# External_WatchDogs.net
KiCad netlist of a schematic drawn in Altium Designer
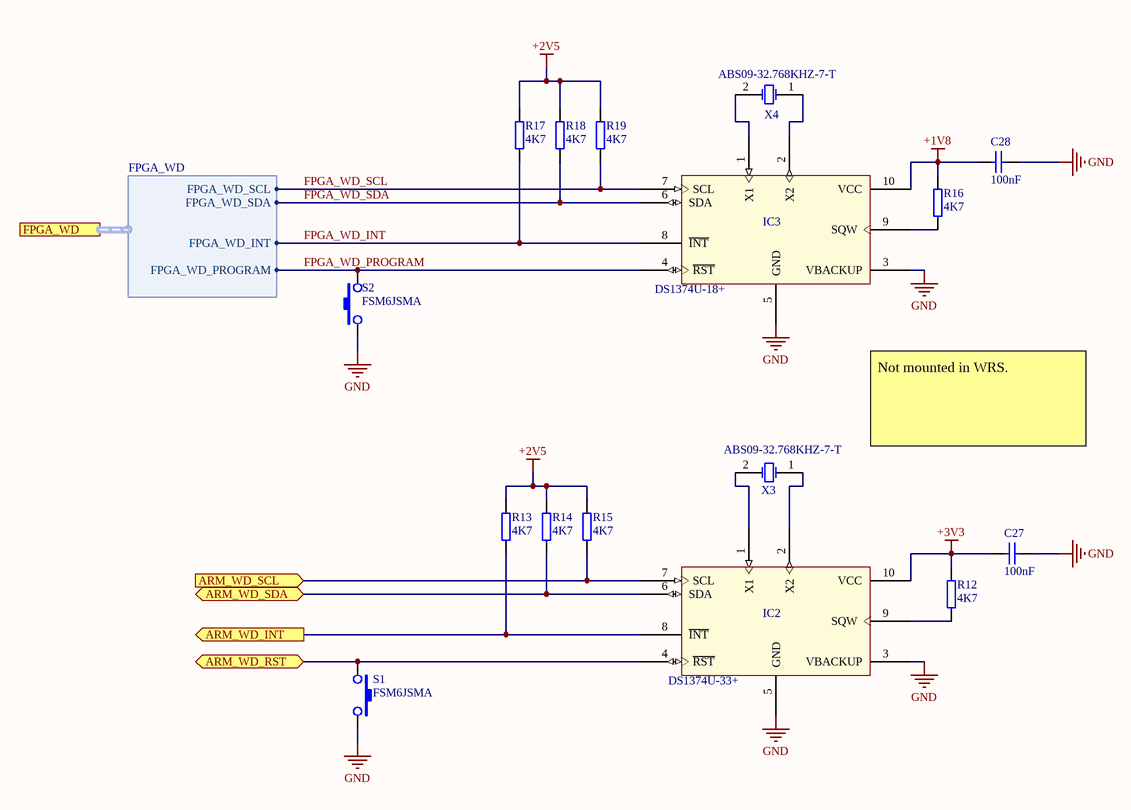
[diagram p0: External WatchDogs.SchDoc]

(export (version "E")
  (design (tool "Eeschema 10.0.6"))
  (components
    (comp (ref "C27")
      (value "100nF")
      (footprint "CC1005-0402")
      (description "Capacitor")
      (fields
        (field (name "TOLERANCE") "±10%")
        (field (name "VOLTAGE") "16V")
        (field (name "PUBLISHER") "Altium Limited")
      )
      (libsource (lib "wr_switch") (part "Cap"))
    )
    (comp (ref "C28")
      (value "100nF")
      (footprint "CC1005-0402")
      (description "Capacitor")
      (fields
        (field (name "TOLERANCE") "±10%")
        (field (name "VOLTAGE") "16V")
        (field (name "PUBLISHER") "Altium Limited")
      )
      (libsource (lib "wr_switch") (part "Cap"))
    )
    (comp (ref "IC2")
      (value "DS1374U-33+")
      (footprint "UMAX10")
      (description "I2C, 32 BIT BINARY COUNTER WATCHDOG RTC")
      (libsource (lib "wr_switch") (part "DS1374"))
    )
    (comp (ref "IC3")
      (value "DS1374U-18+")
      (footprint "UMAX10")
      (description "I2C, 32 BIT BINARY COUNTER WATCHDOG RTC")
      (libsource (lib "wr_switch") (part "DS1374"))
    )
    (comp (ref "R12")
      (value "4K7")
      (footprint "0402")
      (description "SMD Resistor")
      (fields (field (name "TOLERANCE") "±1%"))
      (libsource (lib "wr_switch") (part "RES_SMD"))
    )
    (comp (ref "R13")
      (value "4K7")
      (footprint "0402")
      (description "SMD Resistor")
      (fields (field (name "TOLERANCE") "±1%"))
      (libsource (lib "wr_switch") (part "RES_SMD"))
    )
    (comp (ref "R14")
      (value "4K7")
      (footprint "0402")
      (description "SMD Resistor")
      (fields (field (name "TOLERANCE") "±1%"))
      (libsource (lib "wr_switch") (part "RES_SMD"))
    )
    (comp (ref "R15")
      (value "4K7")
      (footprint "0402")
      (description "SMD Resistor")
      (fields (field (name "TOLERANCE") "±1%"))
      (libsource (lib "wr_switch") (part "RES_SMD"))
    )
    (comp (ref "R16")
      (value "4K7")
      (footprint "0402")
      (description "SMD Resistor")
      (fields (field (name "TOLERANCE") "±1%"))
      (libsource (lib "wr_switch") (part "RES_SMD"))
    )
    (comp (ref "R17")
      (value "4K7")
      (footprint "0402")
      (description "SMD Resistor")
      (fields (field (name "TOLERANCE") "±1%"))
      (libsource (lib "wr_switch") (part "RES_SMD"))
    )
    (comp (ref "R18")
      (value "4K7")
      (footprint "0402")
      (description "SMD Resistor")
      (fields (field (name "TOLERANCE") "±1%"))
      (libsource (lib "wr_switch") (part "RES_SMD"))
    )
    (comp (ref "R19")
      (value "4K7")
      (footprint "0402")
      (description "SMD Resistor")
      (fields (field (name "TOLERANCE") "±1%"))
      (libsource (lib "wr_switch") (part "RES_SMD"))
    )
    (comp (ref "S1")
      (value "FSM6JSMA")
      (footprint "7S_WR:SWITCH-FSM6JSMA")
      (description "Push button")
      (fields (field (name "MANUFACTURER") "Tyco Electronics"))
      (libsource (lib "wr_switch") (part "SW-PB"))
    )
    (comp (ref "S2")
      (value "FSM6JSMA")
      (footprint "7S_WR:SWITCH-FSM6JSMA")
      (description "Push button")
      (fields (field (name "MANUFACTURER") "Tyco Electronics"))
      (libsource (lib "wr_switch") (part "SW-PB"))
    )
    (comp (ref "X3")
      (value "ABS09-32.768KHZ-7-T")
      (footprint "XTAL_abs09")
      (description "Crystal Oscillator 7pF")
      (fields (field (name "MANUFACTURER") "Raltron") (field (name "PUBLISHER") "Altium Limited"))
      (libsource (lib "Miscellaneous Devices") (part "XTAL"))
    )
    (comp (ref "X4")
      (value "ABS09-32.768KHZ-7-T")
      (footprint "XTAL_abs09")
      (description "Crystal Oscillator 7pF")
      (fields (field (name "MANUFACTURER") "Raltron") (field (name "PUBLISHER") "Altium Limited"))
      (libsource (lib "Miscellaneous Devices") (part "XTAL"))
    )
  )
  (nets
    (net (code "2") (name "+1V8") (class "Default")
      (node (ref "C28") (pin "2") (pinfunction "2_2") (pintype "passive"))
      (node (ref "IC3") (pin "10") (pinfunction "VCC_10") (pintype "power_in"))
      (node (ref "R16") (pin "2") (pinfunction "2_2") (pintype "passive"))
    )
    (net (code "3") (name "+2V5") (class "Default")
      (node (ref "R13") (pin "2") (pinfunction "2_2") (pintype "passive"))
      (node (ref "R14") (pin "2") (pinfunction "2_2") (pintype "passive"))
      (node (ref "R15") (pin "2") (pinfunction "2_2") (pintype "passive"))
      (node (ref "R17") (pin "2") (pinfunction "2_2") (pintype "passive"))
      (node (ref "R18") (pin "2") (pinfunction "2_2") (pintype "passive"))
      (node (ref "R19") (pin "2") (pinfunction "2_2") (pintype "passive"))
    )
    (net (code "4") (name "+3V3") (class "Default")
      (node (ref "C27") (pin "2") (pinfunction "2_2") (pintype "passive"))
      (node (ref "IC2") (pin "10") (pinfunction "VCC_10") (pintype "power_in"))
      (node (ref "R12") (pin "2") (pinfunction "2_2") (pintype "passive"))
    )
    (net (code "5") (name "/ARM_WD_INT") (class "Default")
      (node (ref "IC2") (pin "8") (pinfunction "~{INT}_8") (pintype "open_collector"))
      (node (ref "R13") (pin "1") (pinfunction "1_1") (pintype "passive"))
    )
    (net (code "6") (name "/ARM_WD_RST") (class "Default")
      (node (ref "IC2") (pin "4") (pinfunction "~{RST}_4") (pintype "bidirectional"))
      (node (ref "S1") (pin "1") (pinfunction "1_1") (pintype "passive"))
    )
    (net (code "7") (name "/ARM_WD_SCL") (class "Default")
      (node (ref "IC2") (pin "7") (pinfunction "SCL_7") (pintype "input"))
      (node (ref "R15") (pin "1") (pinfunction "1_1") (pintype "passive"))
    )
    (net (code "8") (name "/ARM_WD_SDA") (class "Default")
      (node (ref "IC2") (pin "6") (pinfunction "SDA_6") (pintype "bidirectional"))
      (node (ref "R14") (pin "1") (pinfunction "1_1") (pintype "passive"))
    )
    (net (code "9") (name "/FPGA_WD_INT") (class "Default")
      (node (ref "IC3") (pin "8") (pinfunction "~{INT}_8") (pintype "open_collector"))
      (node (ref "R17") (pin "1") (pinfunction "1_1") (pintype "passive"))
    )
    (net (code "10") (name "/FPGA_WD_PROGRAM") (class "Default")
      (node (ref "IC3") (pin "4") (pinfunction "~{RST}_4") (pintype "bidirectional"))
      (node (ref "S2") (pin "2") (pinfunction "2_2") (pintype "passive"))
    )
    (net (code "11") (name "/FPGA_WD_SCL") (class "Default")
      (node (ref "IC3") (pin "7") (pinfunction "SCL_7") (pintype "input"))
      (node (ref "R19") (pin "1") (pinfunction "1_1") (pintype "passive"))
    )
    (net (code "12") (name "/FPGA_WD_SDA") (class "Default")
      (node (ref "IC3") (pin "6") (pinfunction "SDA_6") (pintype "bidirectional"))
      (node (ref "R18") (pin "1") (pinfunction "1_1") (pintype "passive"))
    )
    (net (code "14") (name "GND") (class "Default")
      (node (ref "C27") (pin "1") (pinfunction "1_1") (pintype "passive"))
      (node (ref "C28") (pin "1") (pinfunction "1_1") (pintype "passive"))
      (node (ref "IC2") (pin "3") (pinfunction "VBACKUP_3") (pintype "power_in"))
      (node (ref "IC2") (pin "5") (pinfunction "GND_5") (pintype "power_in"))
      (node (ref "IC3") (pin "3") (pinfunction "VBACKUP_3") (pintype "power_in"))
      (node (ref "IC3") (pin "5") (pinfunction "GND_5") (pintype "power_in"))
      (node (ref "S1") (pin "2") (pinfunction "2_2") (pintype "passive"))
      (node (ref "S2") (pin "1") (pinfunction "1_1") (pintype "passive"))
    )
    (net (code "15") (name "Net-(IC2-SQW)") (class "Default")
      (node (ref "IC2") (pin "9") (pinfunction "SQW_9") (pintype "open_collector"))
      (node (ref "R12") (pin "1") (pinfunction "1_1") (pintype "passive"))
    )
    (net (code "16") (name "Net-(IC2-X1)") (class "Default")
      (node (ref "IC2") (pin "1") (pinfunction "X1_1") (pintype "input"))
      (node (ref "X3") (pin "2") (pinfunction "OSC2_2") (pintype "passive"))
    )
    (net (code "17") (name "Net-(IC2-X2)") (class "Default")
      (node (ref "IC2") (pin "2") (pinfunction "X2_2") (pintype "output"))
      (node (ref "X3") (pin "1") (pinfunction "OSC1_1") (pintype "passive"))
    )
    (net (code "18") (name "Net-(IC3-SQW)") (class "Default")
      (node (ref "IC3") (pin "9") (pinfunction "SQW_9") (pintype "open_collector"))
      (node (ref "R16") (pin "1") (pinfunction "1_1") (pintype "passive"))
    )
    (net (code "19") (name "Net-(IC3-X1)") (class "Default")
      (node (ref "IC3") (pin "1") (pinfunction "X1_1") (pintype "input"))
      (node (ref "X4") (pin "2") (pinfunction "OSC2_2") (pintype "passive"))
    )
    (net (code "20") (name "Net-(IC3-X2)") (class "Default")
      (node (ref "IC3") (pin "2") (pinfunction "X2_2") (pintype "output"))
      (node (ref "X4") (pin "1") (pinfunction "OSC1_1") (pintype "passive"))
    )
  )
)
